# Schematic.net
KiCad netlist of a schematic drawn in EAGLE
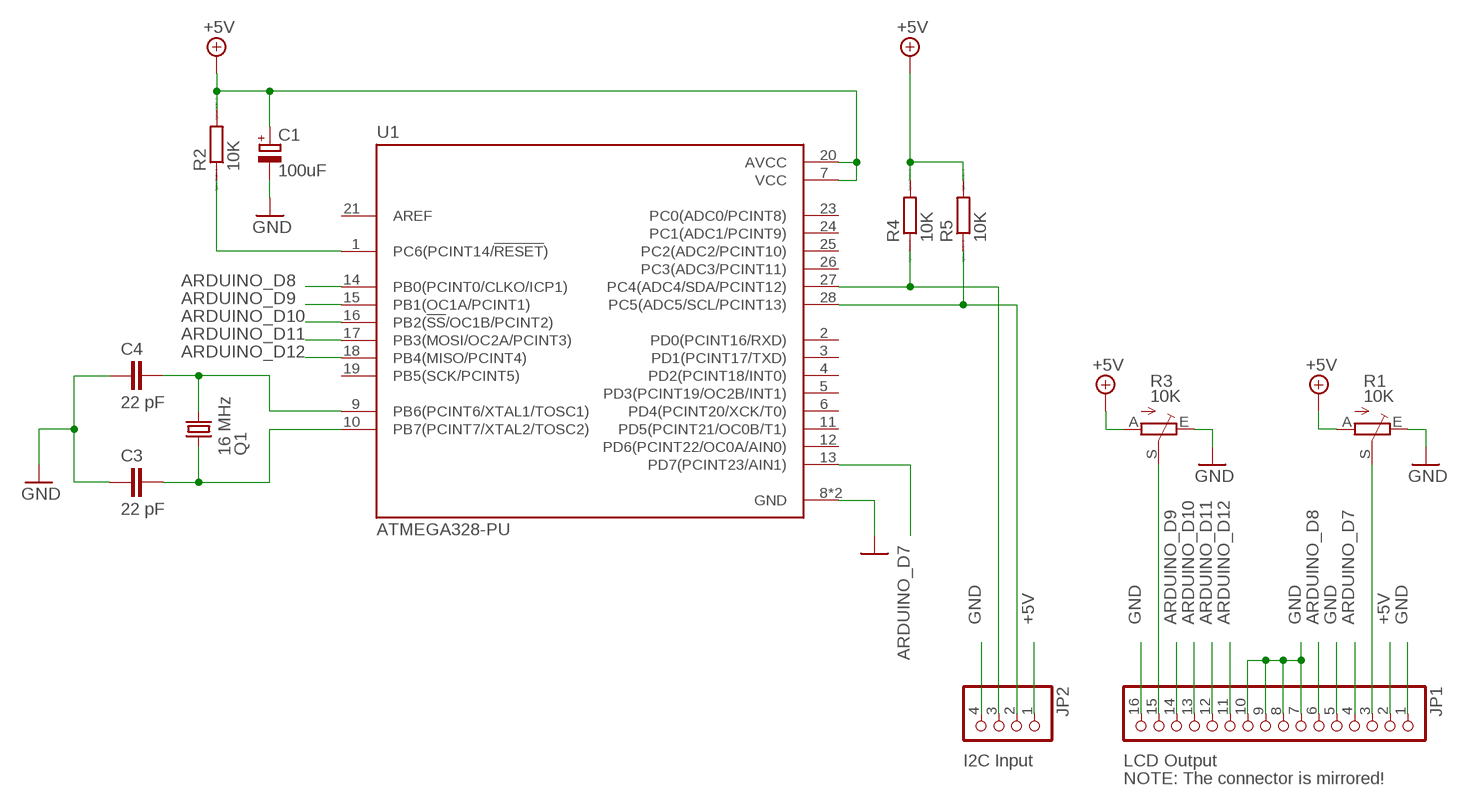
[diagram p0: schematic, sheet 1]

(export (version "E")
  (design (tool "Eeschema 10.0.6"))
  (components
    (comp (ref "C1")
      (value "100uF")
      (footprint "eagle-import:E2,5-6E")
      (libsource (lib "eagle-import") (part "CPOL-EUE2,5-6E"))
    )
    (comp (ref "C3")
      (value "22 pF")
      (footprint "eagle-import:C5B2.5")
      (libsource (lib "eagle-import") (part "C5/2.5"))
    )
    (comp (ref "C4")
      (value "22 pF")
      (footprint "eagle-import:C5B2.5")
      (libsource (lib "eagle-import") (part "C5/2.5"))
    )
    (comp (ref "JP1")
      (value "PINHD-1X16")
      (footprint "eagle-import:1X16")
      (libsource (lib "eagle-import") (part "PINHD-1X16"))
    )
    (comp (ref "JP2")
      (value "PINHD-1X4/90")
      (footprint "eagle-import:1X04_90")
      (libsource (lib "eagle-import") (part "PINHD-1X4/90"))
    )
    (comp (ref "Q1")
      (value "16 MHz")
      (footprint "eagle-import:HC49_S")
      (libsource (lib "eagle-import") (part "CRYSTALHC49S"))
    )
    (comp (ref "R1")
      (value "10K")
      (footprint "eagle-import:B25P")
      (libsource (lib "eagle-import") (part "TRIM_EU-B25P"))
    )
    (comp (ref "R2")
      (value "10K")
      (footprint "eagle-import:0204_7")
      (libsource (lib "eagle-import") (part "R0204/7"))
    )
    (comp (ref "R3")
      (value "10K")
      (footprint "eagle-import:B25P")
      (libsource (lib "eagle-import") (part "TRIM_EU-B25P"))
    )
    (comp (ref "R4")
      (value "10K")
      (footprint "eagle-import:0204_7")
      (libsource (lib "eagle-import") (part "R0204/7"))
    )
    (comp (ref "R5")
      (value "10K")
      (footprint "eagle-import:0204_7")
      (libsource (lib "eagle-import") (part "R0204/7"))
    )
    (comp (ref "U1")
      (value "ATMEGA328-PU")
      (footprint "eagle-import:DIP787W46P254L3467H508Q28")
      (fields (field (name "MF") "Microchip Technology"))
      (libsource (lib "eagle-import") (part "ATMEGA328-PU"))
    )
  )
  (nets
    (net (code "1") (name "+5V") (class "Default")
      (node (ref "C1") (pin "+") (pinfunction "+_+") (pintype "passive"))
      (node (ref "JP1") (pin "2") (pinfunction "2_2") (pintype "passive"))
      (node (ref "JP2") (pin "1") (pinfunction "1_1") (pintype "passive"))
      (node (ref "R1") (pin "A") (pinfunction "A_A") (pintype "passive"))
      (node (ref "R2") (pin "2") (pinfunction "2_2") (pintype "passive"))
      (node (ref "R3") (pin "A") (pinfunction "A_A") (pintype "passive"))
      (node (ref "R4") (pin "2") (pinfunction "2_2") (pintype "passive"))
      (node (ref "R5") (pin "2") (pinfunction "2_2") (pintype "passive"))
      (node (ref "U1") (pin "20") (pinfunction "AVCC_20") (pintype "power_in"))
      (node (ref "U1") (pin "7") (pinfunction "VCC_7") (pintype "power_in"))
    )
    (net (code "2") (name "/ARDUINO_D7") (class "Default")
      (node (ref "JP1") (pin "4") (pinfunction "4_4") (pintype "passive"))
      (node (ref "U1") (pin "13") (pinfunction "PD7(PCINT23/AIN1)_13") (pintype "bidirectional"))
    )
    (net (code "3") (name "/ARDUINO_D8") (class "Default")
      (node (ref "JP1") (pin "6") (pinfunction "6_6") (pintype "passive"))
      (node (ref "U1") (pin "14") (pinfunction "PB0(PCINT0/CLKO/ICP1)_14") (pintype "bidirectional"))
    )
    (net (code "4") (name "/ARDUINO_D9") (class "Default")
      (node (ref "JP1") (pin "14") (pinfunction "14_14") (pintype "passive"))
      (node (ref "U1") (pin "15") (pinfunction "PB1(OC1A/PCINT1)_15") (pintype "bidirectional"))
    )
    (net (code "5") (name "/ARDUINO_D10") (class "Default")
      (node (ref "JP1") (pin "13") (pinfunction "13_13") (pintype "passive"))
      (node (ref "U1") (pin "16") (pinfunction "PB2(~{SS}/OC1B/PCINT2)_16") (pintype "bidirectional"))
    )
    (net (code "6") (name "/ARDUINO_D11") (class "Default")
      (node (ref "JP1") (pin "12") (pinfunction "12_12") (pintype "passive"))
      (node (ref "U1") (pin "17") (pinfunction "PB3(MOSI/OC2A/PCINT3)_17") (pintype "bidirectional"))
    )
    (net (code "7") (name "/ARDUINO_D12") (class "Default")
      (node (ref "JP1") (pin "11") (pinfunction "11_11") (pintype "passive"))
      (node (ref "U1") (pin "18") (pinfunction "PB4(MISO/PCINT4)_18") (pintype "bidirectional"))
    )
    (net (code "8") (name "GND") (class "Default")
      (node (ref "C1") (pin "-") (pinfunction "-_-") (pintype "passive"))
      (node (ref "C3") (pin "1") (pinfunction "1_1") (pintype "passive"))
      (node (ref "C4") (pin "1") (pinfunction "1_1") (pintype "passive"))
      (node (ref "JP1") (pin "1") (pinfunction "1_1") (pintype "passive"))
      (node (ref "JP1") (pin "10") (pinfunction "10_10") (pintype "passive"))
      (node (ref "JP1") (pin "16") (pinfunction "16_16") (pintype "passive"))
      (node (ref "JP1") (pin "5") (pinfunction "5_5") (pintype "passive"))
      (node (ref "JP1") (pin "7") (pinfunction "7_7") (pintype "passive"))
      (node (ref "JP1") (pin "8") (pinfunction "8_8") (pintype "passive"))
      (node (ref "JP1") (pin "9") (pinfunction "9_9") (pintype "passive"))
      (node (ref "JP2") (pin "4") (pinfunction "4_4") (pintype "passive"))
      (node (ref "R1") (pin "E") (pinfunction "E_E") (pintype "passive"))
      (node (ref "R3") (pin "E") (pinfunction "E_E") (pintype "passive"))
      (node (ref "U1") (pin "22") (pinfunction "GND_22") (pintype "power_in"))
      (node (ref "U1") (pin "8") (pinfunction "GND_8") (pintype "power_in"))
    )
    (net (code "9") (name "Net-(JP1-Pad3)") (class "Default")
      (node (ref "JP1") (pin "3") (pinfunction "3_3") (pintype "passive"))
      (node (ref "R1") (pin "S") (pinfunction "S_S") (pintype "passive"))
    )
    (net (code "10") (name "Net-(JP1-Pad15)") (class "Default")
      (node (ref "JP1") (pin "15") (pinfunction "15_15") (pintype "passive"))
      (node (ref "R3") (pin "S") (pinfunction "S_S") (pintype "passive"))
    )
    (net (code "11") (name "Net-(U1-PB6(PCINT6{slash}XTAL1{slash}TOSC1))") (class "Default")
      (node (ref "C4") (pin "2") (pinfunction "2_2") (pintype "passive"))
      (node (ref "Q1") (pin "2") (pinfunction "2_2") (pintype "passive"))
      (node (ref "U1") (pin "9") (pinfunction "PB6(PCINT6/XTAL1/TOSC1)_9") (pintype "bidirectional"))
    )
    (net (code "12") (name "Net-(U1-PB7(PCINT7{slash}XTAL2{slash}TOSC2))") (class "Default")
      (node (ref "C3") (pin "2") (pinfunction "2_2") (pintype "passive"))
      (node (ref "Q1") (pin "1") (pinfunction "1_1") (pintype "passive"))
      (node (ref "U1") (pin "10") (pinfunction "PB7(PCINT7/XTAL2/TOSC2)_10") (pintype "bidirectional"))
    )
    (net (code "13") (name "Net-(U1-PC4(ADC4{slash}SDA{slash}PCINT12))") (class "Default")
      (node (ref "JP2") (pin "3") (pinfunction "3_3") (pintype "passive"))
      (node (ref "R4") (pin "1") (pinfunction "1_1") (pintype "passive"))
      (node (ref "U1") (pin "27") (pinfunction "PC4(ADC4/SDA/PCINT12)_27") (pintype "bidirectional"))
    )
    (net (code "14") (name "Net-(U1-PC5(ADC5{slash}SCL{slash}PCINT13))") (class "Default")
      (node (ref "JP2") (pin "2") (pinfunction "2_2") (pintype "passive"))
      (node (ref "R5") (pin "1") (pinfunction "1_1") (pintype "passive"))
      (node (ref "U1") (pin "28") (pinfunction "PC5(ADC5/SCL/PCINT13)_28") (pintype "bidirectional"))
    )
    (net (code "15") (name "Net-(U1-PC6(PCINT14{slash}~{RESET}))") (class "Default")
      (node (ref "R2") (pin "1") (pinfunction "1_1") (pintype "passive"))
      (node (ref "U1") (pin "1") (pinfunction "PC6(PCINT14/~{RESET})_1") (pintype "bidirectional"))
    )
    (net (code "16") (name "unconnected-(U1-AREF-Pad21)") (class "Default")
      (node (ref "U1") (pin "21") (pinfunction "AREF_21") (pintype "input"))
    )
    (net (code "17") (name "unconnected-(U1-PB5(SCK{slash}PCINT5)-Pad19)") (class "Default")
      (node (ref "U1") (pin "19") (pinfunction "PB5(SCK/PCINT5)_19") (pintype "bidirectional"))
    )
    (net (code "18") (name "unconnected-(U1-PC0(ADC0{slash}PCINT8)-Pad23)") (class "Default")
      (node (ref "U1") (pin "23") (pinfunction "PC0(ADC0/PCINT8)_23") (pintype "bidirectional"))
    )
    (net (code "19") (name "unconnected-(U1-PC1(ADC1{slash}PCINT9)-Pad24)") (class "Default")
      (node (ref "U1") (pin "24") (pinfunction "PC1(ADC1/PCINT9)_24") (pintype "bidirectional"))
    )
    (net (code "20") (name "unconnected-(U1-PC2(ADC2{slash}PCINT10)-Pad25)") (class "Default")
      (node (ref "U1") (pin "25") (pinfunction "PC2(ADC2/PCINT10)_25") (pintype "bidirectional"))
    )
    (net (code "21") (name "unconnected-(U1-PC3(ADC3{slash}PCINT11)-Pad26)") (class "Default")
      (node (ref "U1") (pin "26") (pinfunction "PC3(ADC3/PCINT11)_26") (pintype "bidirectional"))
    )
    (net (code "22") (name "unconnected-(U1-PD0(PCINT16{slash}RXD)-Pad2)") (class "Default")
      (node (ref "U1") (pin "2") (pinfunction "PD0(PCINT16/RXD)_2") (pintype "bidirectional"))
    )
    (net (code "23") (name "unconnected-(U1-PD1(PCINT17{slash}TXD)-Pad3)") (class "Default")
      (node (ref "U1") (pin "3") (pinfunction "PD1(PCINT17/TXD)_3") (pintype "bidirectional"))
    )
    (net (code "24") (name "unconnected-(U1-PD2(PCINT18{slash}INT0)-Pad4)") (class "Default")
      (node (ref "U1") (pin "4") (pinfunction "PD2(PCINT18/INT0)_4") (pintype "bidirectional"))
    )
    (net (code "25") (name "unconnected-(U1-PD3(PCINT19{slash}OC2B{slash}INT1)-Pad5)") (class "Default")
      (node (ref "U1") (pin "5") (pinfunction "PD3(PCINT19/OC2B/INT1)_5") (pintype "bidirectional"))
    )
    (net (code "26") (name "unconnected-(U1-PD4(PCINT20{slash}XCK{slash}T0)-Pad6)") (class "Default")
      (node (ref "U1") (pin "6") (pinfunction "PD4(PCINT20/XCK/T0)_6") (pintype "bidirectional"))
    )
    (net (code "27") (name "unconnected-(U1-PD5(PCINT21{slash}OC0B{slash}T1)-Pad11)") (class "Default")
      (node (ref "U1") (pin "11") (pinfunction "PD5(PCINT21/OC0B/T1)_11") (pintype "bidirectional"))
    )
    (net (code "28") (name "unconnected-(U1-PD6(PCINT22{slash}OC0A{slash}AIN0)-Pad12)") (class "Default")
      (node (ref "U1") (pin "12") (pinfunction "PD6(PCINT22/OC0A/AIN0)_12") (pintype "bidirectional"))
    )
  )
)
